# PowerMgt.net
KiCad netlist of a schematic drawn in Altium Designer
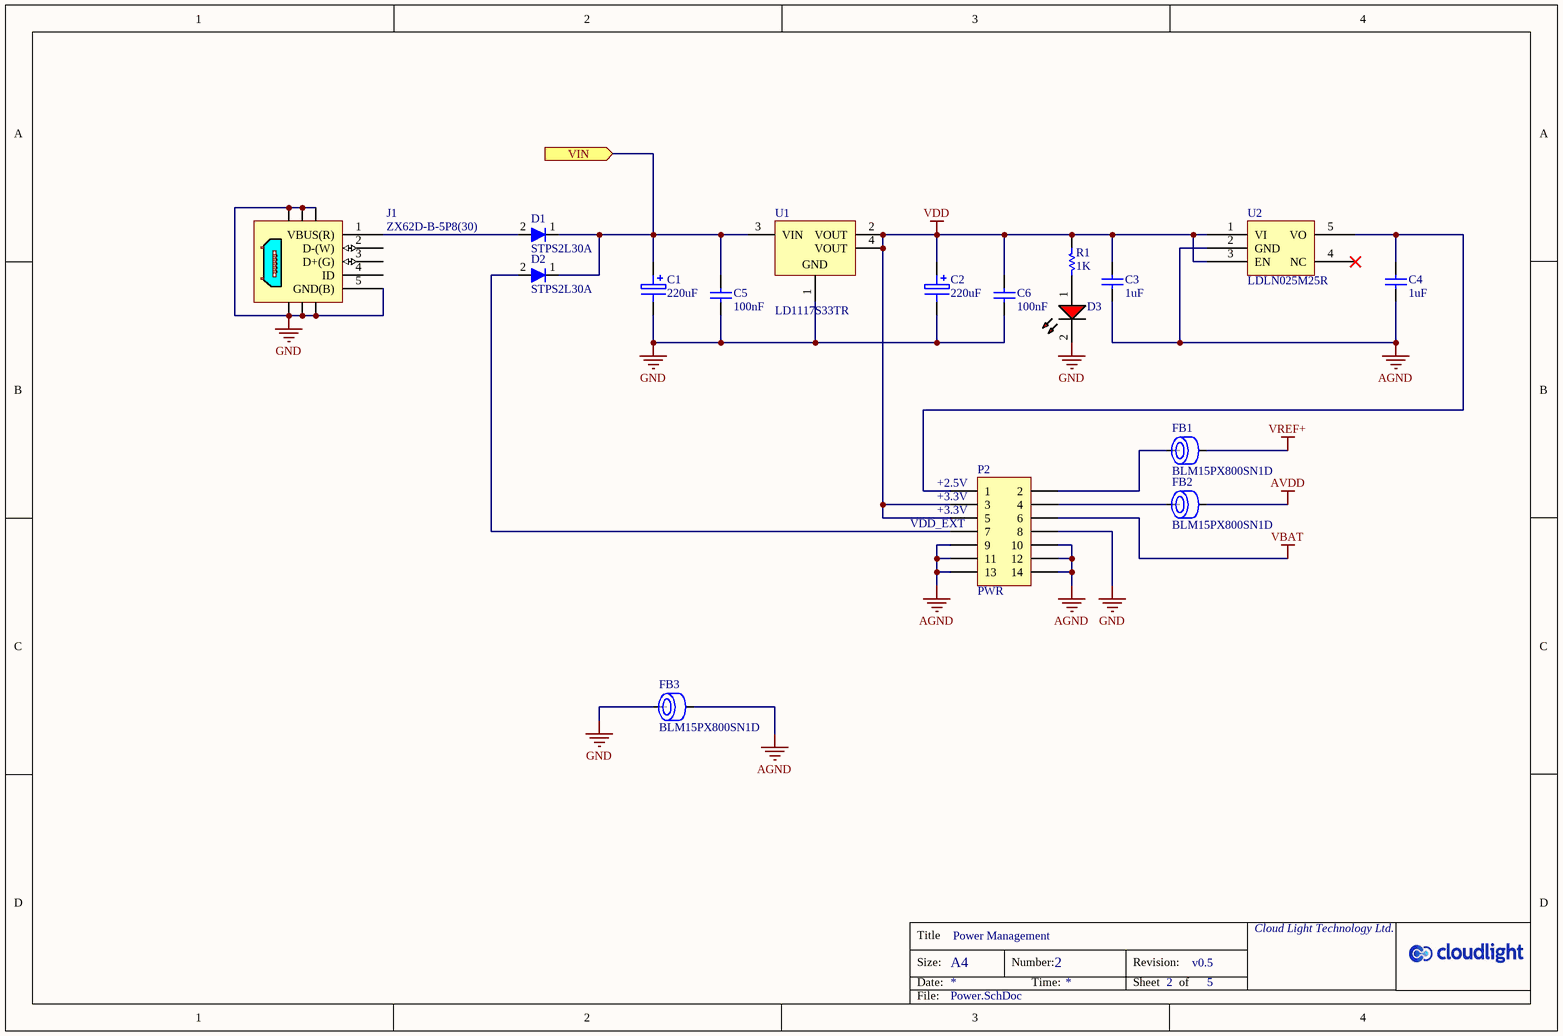
[diagram p0: PowerMgt.SchDoc]

(export (version "E")
  (design (tool "Eeschema 10.0.6"))
  (components
    (comp (ref "C1")
      (value "220uF")
      (footprint "SMD-EC-F6.3")
      (description "220μF 16V Aluminum Electrolytic Capacitors Radial, Can - SMD 160 mohm @ 100kHz 2000 Hrs @ 105°C")
      (fields
        (field (name "MANUFACTURER") "Panasonic Electronic Components")
        (field (name "PARTNUMBER") "EEE-FPC221XAP")
      )
      (libsource (lib "Panasonic Aluminum Electrolytic Capacitors (Surface Mount Type)") (part "EEE-FPC221XAP"))
    )
    (comp (ref "C2")
      (value "220uF")
      (footprint "SMD-EC-F6.3")
      (description "220μF 16V Aluminum Electrolytic Capacitors Radial, Can - SMD 160 mohm @ 100kHz 2000 Hrs @ 105°C")
      (fields
        (field (name "MANUFACTURER") "Panasonic Electronic Components")
        (field (name "PARTNUMBER") "EEE-FPC221XAP")
      )
      (libsource (lib "Panasonic Aluminum Electrolytic Capacitors (Surface Mount Type)") (part "EEE-FPC221XAP"))
    )
    (comp (ref "C3")
      (value "1uF")
      (footprint "CAPC1608N")
      (description "Chip Capacitor")
      (fields (field (name "MANUFACTURER") "[N/A]") (field (name "PUBLISHER") "Wentao SUN"))
      (libsource (lib "Misc Chip Component") (part "Chip Capacitor"))
    )
    (comp (ref "C4")
      (value "1uF")
      (footprint "CAPC1608N")
      (description "Chip Capacitor")
      (fields (field (name "MANUFACTURER") "[N/A]") (field (name "PUBLISHER") "Wentao SUN"))
      (libsource (lib "Misc Chip Component") (part "Chip Capacitor"))
    )
    (comp (ref "C5")
      (value "100nF")
      (footprint "CAPC1608N")
      (description "Chip Capacitor")
      (fields (field (name "MANUFACTURER") "[N/A]") (field (name "PUBLISHER") "Wentao SUN"))
      (libsource (lib "Misc Chip Component") (part "Chip Capacitor"))
    )
    (comp (ref "C6")
      (value "100nF")
      (footprint "CAPC1608N")
      (description "Chip Capacitor")
      (fields (field (name "MANUFACTURER") "[N/A]") (field (name "PUBLISHER") "Wentao SUN"))
      (libsource (lib "Misc Chip Component") (part "Chip Capacitor"))
    )
    (comp (ref "D1")
      (value "STPS2L30A")
      (footprint "DIOM4326X25N")
      (description "Diode Schottky 30V 2A Surface Mount SMA")
      (fields (field (name "MANUFACTURER") "STMicroelectronics") (field (name "PUBLISHER") "Wentao SUN"))
      (libsource (lib "STMicroelectronics Diode Power Schottky Low VF") (part "STPS2L30A"))
    )
    (comp (ref "D2")
      (value "STPS2L30A")
      (footprint "DIOM4326X25N")
      (description "Diode Schottky 30V 2A Surface Mount SMA")
      (fields (field (name "MANUFACTURER") "STMicroelectronics") (field (name "PUBLISHER") "Wentao SUN"))
      (libsource (lib "STMicroelectronics Diode Power Schottky Low VF") (part "STPS2L30A"))
    )
    (comp (ref "D3")
      (value "LED-SMD0603-R")
      (footprint "CD1608-0603")
      (description "Single Color LED Indication, 0603, Red")
      (fields (field (name "MANUFACTURER") "[N/A]") (field (name "PUBLISHER") "Wentao SUN"))
      (libsource (lib "Misc LED") (part "LED-SMD0603-R"))
    )
    (comp (ref "FB1")
      (value "BLM15PX800SN1D")
      (footprint "FBC1005N")
      (description "80 Ohms @ 100MHz 1 Power Line Ferrite Bead 0402 (1005 Metric) 2.3A 38mOhm")
      (fields
        (field (name "MANUFACTURER") "Murata Electronics North America")
        (field (name "PUBLISHER") "Wentao SUN")
      )
      (libsource (lib "Misc Chip Component") (part "Ferrite Bead"))
    )
    (comp (ref "FB2")
      (value "BLM15PX800SN1D")
      (footprint "FBC1005N")
      (description "80 Ohms @ 100MHz 1 Power Line Ferrite Bead 0402 (1005 Metric) 2.3A 38mOhm")
      (fields
        (field (name "MANUFACTURER") "Murata Electronics North America")
        (field (name "PUBLISHER") "Wentao SUN")
      )
      (libsource (lib "Misc Chip Component") (part "Ferrite Bead"))
    )
    (comp (ref "FB3")
      (value "BLM15PX800SN1D")
      (footprint "FBC1005N")
      (description "80 Ohms @ 100MHz 1 Power Line Ferrite Bead 0402 (1005 Metric) 2.3A 38mOhm")
      (fields
        (field (name "MANUFACTURER") "Murata Electronics North America")
        (field (name "PUBLISHER") "Wentao SUN")
      )
      (libsource (lib "Misc Chip Component") (part "Ferrite Bead"))
    )
    (comp (ref "J1")
      (value "ZX62D-B-5P8(30)")
      (footprint "USB2.0-4H5")
      (description "USB - micro B USB 2.0 Receptacle Connector 5-Pin")
      (fields (field (name "MANUFACTURER") "Hirose Electric Co Ltd"))
      (libsource (lib "Misc Connector") (part "ZX62D-B-5P8(30)"))
    )
    (comp (ref "P2")
      (value "PWR")
      (footprint "HDR2X7")
      (description "Header, 7-Pin, Dual row")
      (fields (field (name "MANUFACTURER") "[N/A]") (field (name "PUBLISHER") "Altium Limited"))
      (libsource (lib "Miscellaneous Connectors") (part "Header 7X2"))
    )
    (comp (ref "R1")
      (value "1K")
      (footprint "RESC1608N")
      (description "Chip Resistor")
      (fields (field (name "MANUFACTURER") "[N/A]") (field (name "PUBLISHER") "Wentao SUN"))
      (libsource (lib "Misc Chip Component") (part "Chip Resistor"))
    )
    (comp (ref "U1")
      (value "LD1117S33TR")
      (footprint "SOT-223_N")
      (description "Fixed Low Drop Positive Voltage Regulator, 3.3V, 4-Pin SOT-223, Tape and Reel")
      (fields (field (name "MANUFACTURER") "STMicroelectronics"))
      (libsource (lib "STMicroelectronics Power Management Linear Regulator") (part "LD1117S33TR"))
    )
    (comp (ref "U2")
      (value "LDLN025M25R")
      (footprint "SOT95P280X145-5N")
      (description "Linear Voltage Regulator IC  1 Output  250mA SOT-23-5")
      (fields (field (name "MANUFACTURER") "STMicroelectronics"))
      (libsource (lib "STMicroelectronics Power Management High PSRR LDO Regulators") (part "LDLN025M25R"))
    )
  )
  (nets
    (net (code "1") (name "/VIN") (class "Default")
      (node (ref "C1") (pin "1") (pinfunction "1_1") (pintype "passive"))
      (node (ref "C5") (pin "2") (pinfunction "2_2") (pintype "passive"))
      (node (ref "D1") (pin "1") (pinfunction "K_1") (pintype "passive"))
      (node (ref "D2") (pin "1") (pinfunction "K_1") (pintype "passive"))
      (node (ref "U1") (pin "3") (pinfunction "VIN_3") (pintype "power_in"))
    )
    (net (code "2") (name "AGND") (class "Default")
      (node (ref "C3") (pin "1") (pinfunction "1_1") (pintype "passive"))
      (node (ref "C4") (pin "1") (pinfunction "1_1") (pintype "passive"))
      (node (ref "FB3") (pin "2") (pinfunction "2_2") (pintype "passive"))
      (node (ref "P2") (pin "10") (pinfunction "10_10") (pintype "passive"))
      (node (ref "P2") (pin "11") (pinfunction "11_11") (pintype "passive"))
      (node (ref "P2") (pin "12") (pinfunction "12_12") (pintype "passive"))
      (node (ref "P2") (pin "13") (pinfunction "13_13") (pintype "passive"))
      (node (ref "P2") (pin "14") (pinfunction "14_14") (pintype "passive"))
      (node (ref "P2") (pin "9") (pinfunction "9_9") (pintype "passive"))
      (node (ref "U2") (pin "2") (pinfunction "GND_2") (pintype "passive"))
    )
    (net (code "3") (name "AVDD") (class "Default")
      (node (ref "FB2") (pin "2") (pinfunction "2_2") (pintype "passive"))
    )
    (net (code "4") (name "GND") (class "Default")
      (node (ref "C1") (pin "2") (pinfunction "2_2") (pintype "passive"))
      (node (ref "C2") (pin "2") (pinfunction "2_2") (pintype "passive"))
      (node (ref "C5") (pin "1") (pinfunction "1_1") (pintype "passive"))
      (node (ref "C6") (pin "1") (pinfunction "1_1") (pintype "passive"))
      (node (ref "D3") (pin "2") (pinfunction "RK_2") (pintype "passive"))
      (node (ref "FB3") (pin "1") (pinfunction "1_1") (pintype "passive"))
      (node (ref "J1") (pin "10") (pinfunction "10_10") (pintype "passive"))
      (node (ref "J1") (pin "11") (pinfunction "11_11") (pintype "passive"))
      (node (ref "J1") (pin "5") (pinfunction "GND(B)_5") (pintype "power_in"))
      (node (ref "J1") (pin "6") (pinfunction "6_6") (pintype "passive"))
      (node (ref "J1") (pin "7") (pinfunction "7_7") (pintype "passive"))
      (node (ref "J1") (pin "8") (pinfunction "8_8") (pintype "passive"))
      (node (ref "J1") (pin "9") (pinfunction "9_9") (pintype "passive"))
      (node (ref "P2") (pin "8") (pinfunction "8_8") (pintype "passive"))
      (node (ref "U1") (pin "1") (pinfunction "GND_1") (pintype "power_in"))
    )
    (net (code "5") (name "Net-(D1-A)") (class "Default")
      (node (ref "D1") (pin "2") (pinfunction "A_2") (pintype "passive"))
      (node (ref "J1") (pin "1") (pinfunction "VBUS(R)_1") (pintype "power_in"))
    )
    (net (code "6") (name "Net-(D2-A)") (class "Default")
      (node (ref "D2") (pin "2") (pinfunction "A_2") (pintype "passive"))
      (node (ref "P2") (pin "7") (pinfunction "7_7") (pintype "passive"))
    )
    (net (code "7") (name "Net-(D3-RA)") (class "Default")
      (node (ref "D3") (pin "1") (pinfunction "RA_1") (pintype "passive"))
      (node (ref "R1") (pin "2") (pinfunction "2_2") (pintype "passive"))
    )
    (net (code "8") (name "Net-(FB1-Pad1)") (class "Default")
      (node (ref "FB1") (pin "1") (pinfunction "1_1") (pintype "passive"))
      (node (ref "P2") (pin "2") (pinfunction "2_2") (pintype "passive"))
    )
    (net (code "9") (name "Net-(FB2-Pad1)") (class "Default")
      (node (ref "FB2") (pin "1") (pinfunction "1_1") (pintype "passive"))
      (node (ref "P2") (pin "4") (pinfunction "4_4") (pintype "passive"))
    )
    (net (code "10") (name "Net-(U2-VO)") (class "Default")
      (node (ref "C4") (pin "2") (pinfunction "2_2") (pintype "passive"))
      (node (ref "P2") (pin "1") (pinfunction "1_1") (pintype "passive"))
      (node (ref "U2") (pin "5") (pinfunction "VO_5") (pintype "passive"))
    )
    (net (code "11") (name "VBAT") (class "Default")
      (node (ref "P2") (pin "6") (pinfunction "6_6") (pintype "passive"))
    )
    (net (code "12") (name "VDD") (class "Default")
      (node (ref "C2") (pin "1") (pinfunction "1_1") (pintype "passive"))
      (node (ref "C3") (pin "2") (pinfunction "2_2") (pintype "passive"))
      (node (ref "C6") (pin "2") (pinfunction "2_2") (pintype "passive"))
      (node (ref "P2") (pin "3") (pinfunction "3_3") (pintype "passive"))
      (node (ref "P2") (pin "5") (pinfunction "5_5") (pintype "passive"))
      (node (ref "R1") (pin "1") (pinfunction "1_1") (pintype "passive"))
      (node (ref "U1") (pin "2") (pinfunction "VOUT_2") (pintype "power_in"))
      (node (ref "U1") (pin "4") (pinfunction "VOUT_4") (pintype "power_in"))
      (node (ref "U2") (pin "1") (pinfunction "VI_1") (pintype "passive"))
      (node (ref "U2") (pin "3") (pinfunction "EN_3") (pintype "passive"))
    )
    (net (code "13") (name "VREF+") (class "Default")
      (node (ref "FB1") (pin "2") (pinfunction "2_2") (pintype "passive"))
    )
    (net (code "14") (name "unconnected-(J1-D+(G)-Pad3)") (class "Default")
      (node (ref "J1") (pin "3") (pinfunction "D+(G)_3") (pintype "bidirectional"))
    )
    (net (code "15") (name "unconnected-(J1-D-(W)-Pad2)") (class "Default")
      (node (ref "J1") (pin "2") (pinfunction "D-(W)_2") (pintype "bidirectional"))
    )
    (net (code "16") (name "unconnected-(J1-ID-Pad4)") (class "Default")
      (node (ref "J1") (pin "4") (pinfunction "ID_4") (pintype "passive"))
    )
    (net (code "17") (name "unconnected-(U2-NC-Pad4)") (class "Default")
      (node (ref "U2") (pin "4") (pinfunction "NC_4") (pintype "passive+no_connect"))
    )
  )
)
